# sensor-fade.net
KiCad netlist of a schematic drawn in EAGLE
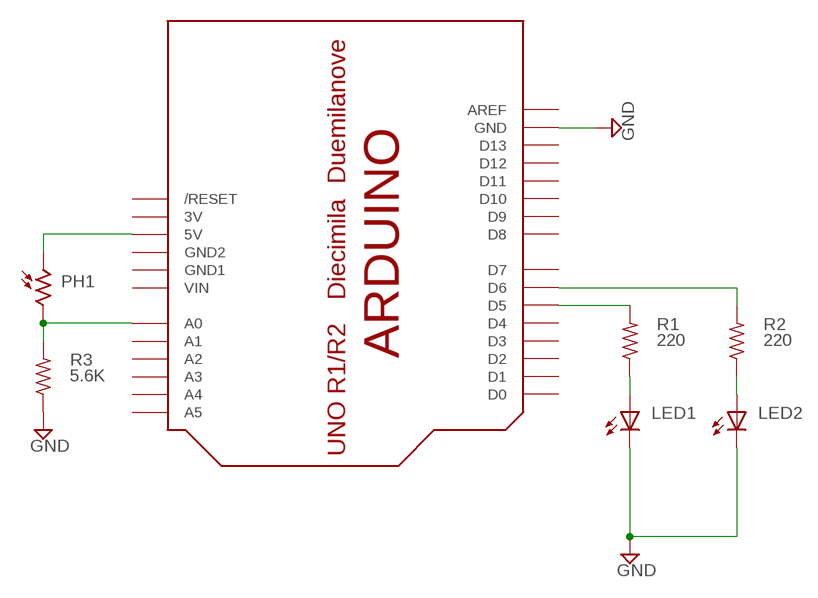
[diagram p0: schematic, sheet 1]

(export (version "E")
  (design (tool "Eeschema 10.0.6"))
  (components
    (comp (ref "LED1")
      (value "LED5MM")
      (footprint "eagle-import:LED5MM")
      (libsource (lib "eagle-import") (part "LED5MM"))
    )
    (comp (ref "LED2")
      (value "LED5MM")
      (footprint "eagle-import:LED5MM")
      (libsource (lib "eagle-import") (part "LED5MM"))
    )
    (comp (ref "PH1")
      (value "A1050_09")
      (footprint "eagle-import:T0-46-A10XX")
      (libsource (lib "eagle-import") (part "A1050_09"))
    )
    (comp (ref "R1")
      (value "220")
      (footprint "eagle-import:0204_7")
      (libsource (lib "eagle-import") (part "R-US_0204/7"))
    )
    (comp (ref "R2")
      (value "220")
      (footprint "eagle-import:0204_7")
      (libsource (lib "eagle-import") (part "R-US_0204/7"))
    )
    (comp (ref "R3")
      (value "5.6K")
      (footprint "eagle-import:0204_7")
      (libsource (lib "eagle-import") (part "R-US_0204/7"))
    )
    (comp (ref "U$1")
      (value "ARDUINOUNO")
      (footprint "eagle-import:ARDUINO")
      (libsource (lib "eagle-import") (part "ARDUINOUNO"))
    )
  )
  (nets
    (net (code "1") (name "/3V") (class "Default")
      (node (ref "U$1") (pin "3V") (pinfunction "3V_3V") (pintype "power_in"))
    )
    (net (code "2") (name "/GND1") (class "Default")
      (node (ref "U$1") (pin "GND1") (pinfunction "GND1_GND1") (pintype "power_in"))
    )
    (net (code "3") (name "/GND2") (class "Default")
      (node (ref "U$1") (pin "GND2") (pinfunction "GND2_GND2") (pintype "power_in"))
    )
    (net (code "4") (name "/VIN") (class "Default")
      (node (ref "U$1") (pin "VIN") (pinfunction "VIN_VIN") (pintype "power_in"))
    )
    (net (code "5") (name "GND") (class "Default")
      (node (ref "LED1") (pin "K") (pinfunction "C_K") (pintype "passive"))
      (node (ref "LED2") (pin "K") (pinfunction "C_K") (pintype "passive"))
      (node (ref "R3") (pin "1") (pinfunction "1_1") (pintype "passive"))
      (node (ref "U$1") (pin "GND") (pinfunction "GND_GND") (pintype "power_in"))
    )
    (net (code "6") (name "Net-(LED1-PadA)") (class "Default")
      (node (ref "LED1") (pin "A") (pinfunction "A_A") (pintype "passive"))
      (node (ref "R1") (pin "1") (pinfunction "1_1") (pintype "passive"))
    )
    (net (code "7") (name "Net-(LED2-PadA)") (class "Default")
      (node (ref "LED2") (pin "A") (pinfunction "A_A") (pintype "passive"))
      (node (ref "R2") (pin "1") (pinfunction "1_1") (pintype "passive"))
    )
    (net (code "8") (name "Net-(PH1-Pad1)") (class "Default")
      (node (ref "PH1") (pin "1") (pinfunction "1_1") (pintype "passive"))
      (node (ref "U$1") (pin "5V") (pinfunction "5V_5V") (pintype "power_in"))
    )
    (net (code "9") (name "Net-(PH1-Pad2)") (class "Default")
      (node (ref "PH1") (pin "2") (pinfunction "2_2") (pintype "passive"))
      (node (ref "R3") (pin "2") (pinfunction "2_2") (pintype "passive"))
      (node (ref "U$1") (pin "A0") (pinfunction "A0_A0") (pintype "bidirectional"))
    )
    (net (code "10") (name "Net-(R1-Pad2)") (class "Default")
      (node (ref "R1") (pin "2") (pinfunction "2_2") (pintype "passive"))
      (node (ref "U$1") (pin "D5") (pinfunction "D5_D5") (pintype "bidirectional"))
    )
    (net (code "11") (name "Net-(R2-Pad2)") (class "Default")
      (node (ref "R2") (pin "2") (pinfunction "2_2") (pintype "passive"))
      (node (ref "U$1") (pin "D6") (pinfunction "D6_D6") (pintype "bidirectional"))
    )
    (net (code "12") (name "unconnected-(U$1-PadA1)") (class "Default")
      (node (ref "U$1") (pin "A1") (pinfunction "A1_A1") (pintype "bidirectional"))
    )
    (net (code "13") (name "unconnected-(U$1-PadA2)") (class "Default")
      (node (ref "U$1") (pin "A2") (pinfunction "A2_A2") (pintype "bidirectional"))
    )
    (net (code "14") (name "unconnected-(U$1-PadA3)") (class "Default")
      (node (ref "U$1") (pin "A3") (pinfunction "A3_A3") (pintype "bidirectional"))
    )
    (net (code "15") (name "unconnected-(U$1-PadA4)") (class "Default")
      (node (ref "U$1") (pin "A4") (pinfunction "A4_A4") (pintype "bidirectional"))
    )
    (net (code "16") (name "unconnected-(U$1-PadA5)") (class "Default")
      (node (ref "U$1") (pin "A5") (pinfunction "A5_A5") (pintype "bidirectional"))
    )
    (net (code "17") (name "unconnected-(U$1-PadAREF)") (class "Default")
      (node (ref "U$1") (pin "AREF") (pinfunction "AREF_AREF") (pintype "bidirectional"))
    )
    (net (code "18") (name "unconnected-(U$1-PadD0)") (class "Default")
      (node (ref "U$1") (pin "D0") (pinfunction "D0_D0") (pintype "bidirectional"))
    )
    (net (code "19") (name "unconnected-(U$1-PadD1)") (class "Default")
      (node (ref "U$1") (pin "D1") (pinfunction "D1_D1") (pintype "bidirectional"))
    )
    (net (code "20") (name "unconnected-(U$1-PadD2)") (class "Default")
      (node (ref "U$1") (pin "D2") (pinfunction "D2_D2") (pintype "bidirectional"))
    )
    (net (code "21") (name "unconnected-(U$1-PadD3)") (class "Default")
      (node (ref "U$1") (pin "D3") (pinfunction "D3_D3") (pintype "bidirectional"))
    )
    (net (code "22") (name "unconnected-(U$1-PadD4)") (class "Default")
      (node (ref "U$1") (pin "D4") (pinfunction "D4_D4") (pintype "bidirectional"))
    )
    (net (code "23") (name "unconnected-(U$1-PadD7)") (class "Default")
      (node (ref "U$1") (pin "D7") (pinfunction "D7_D7") (pintype "bidirectional"))
    )
    (net (code "24") (name "unconnected-(U$1-PadD8)") (class "Default")
      (node (ref "U$1") (pin "D8") (pinfunction "D8_D8") (pintype "bidirectional"))
    )
    (net (code "25") (name "unconnected-(U$1-PadD9)") (class "Default")
      (node (ref "U$1") (pin "D9") (pinfunction "D9_D9") (pintype "bidirectional"))
    )
    (net (code "26") (name "unconnected-(U$1-PadD10)") (class "Default")
      (node (ref "U$1") (pin "D10") (pinfunction "D10_D10") (pintype "bidirectional"))
    )
    (net (code "27") (name "unconnected-(U$1-PadD11)") (class "Default")
      (node (ref "U$1") (pin "D11") (pinfunction "D11_D11") (pintype "bidirectional"))
    )
    (net (code "28") (name "unconnected-(U$1-PadD12)") (class "Default")
      (node (ref "U$1") (pin "D12") (pinfunction "D12_D12") (pintype "bidirectional"))
    )
    (net (code "29") (name "unconnected-(U$1-PadD13)") (class "Default")
      (node (ref "U$1") (pin "D13") (pinfunction "D13_D13") (pintype "bidirectional"))
    )
    (net (code "30") (name "unconnected-(U$1-{slash}RESET-PadRESET)") (class "Default")
      (node (ref "U$1") (pin "RESET") (pinfunction "/RESET_RESET") (pintype "bidirectional"))
    )
  )
)
